# pwrmngmnt.net
KiCad netlist of a schematic drawn in Altium Designer
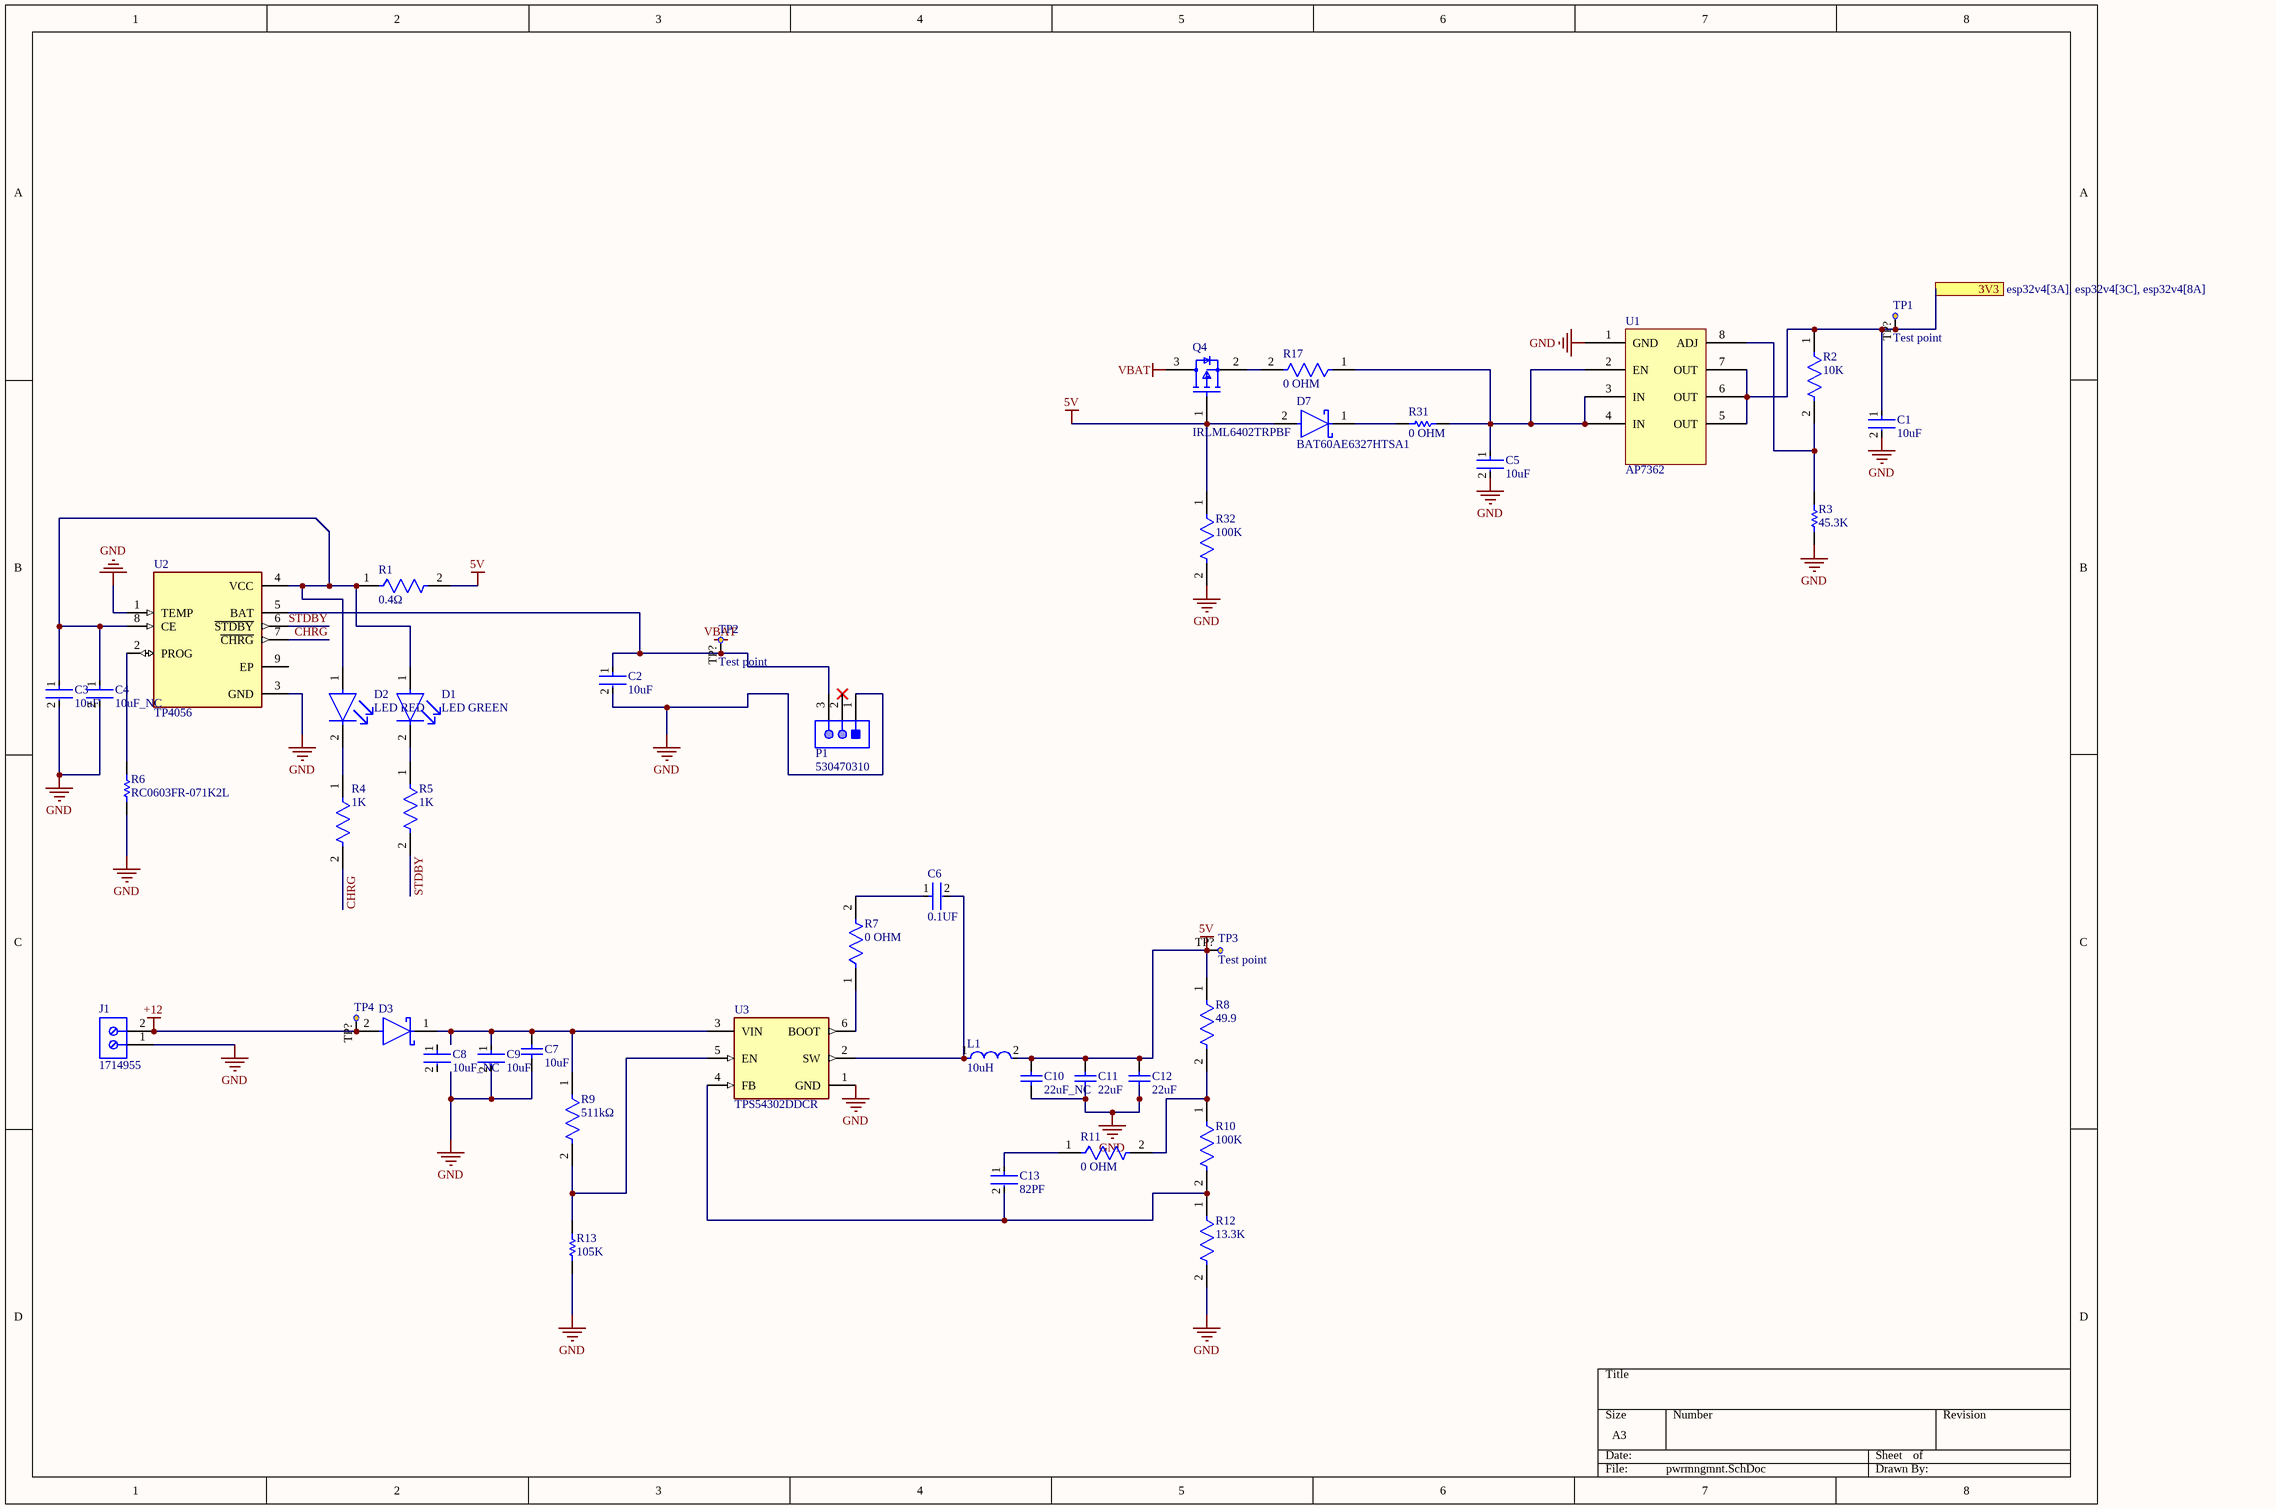
[diagram p0: pwrmngmnt.SchDoc]

(export (version "E")
  (design (tool "Eeschema 10.0.6"))
  (components
    (comp (ref "C1")
      (value "10uF")
      (footprint "FP-GRM21B-0_1-IPC_C")
      (description "Chip Multilayer Ceramic Capacitors for General Purpose, 0805, 10uF, X5R, 15%, 10%, 16V")
      (fields (field (name "TOLERANCE") "10%") (field (name "VOLTAGE") "16V"))
      (libsource (lib "Altium Content Vault") (part "b4654b650e69147ec39a6b967a45e02"))
    )
    (comp (ref "C2")
      (value "10uF")
      (footprint "FP-1210-L_3_3_0_4-W_2_5_0-IPC_B")
      (description "General Purpose Ceramic Capacitor, 1210, 10uF, 10%, X7R, 15%, 50V")
      (fields (field (name "TOLERANCE") "10%") (field (name "VOLTAGE") "50V"))
      (libsource (lib "Altium Content Vault") (part "b4654b650e69147ec39a6b967a45e02"))
    )
    (comp (ref "C3")
      (value "10uF")
      (footprint "FP-GRM21B-0_1-IPC_C")
      (description "Chip Multilayer Ceramic Capacitors for General Purpose, 0805, 10uF, X5R, 15%, 10%, 16V")
      (fields (field (name "TOLERANCE") "10%") (field (name "VOLTAGE") "16V"))
      (libsource (lib "Altium Content Vault") (part "b4654b650e69147ec39a6b967a45e02"))
    )
    (comp (ref "C4")
      (value "10uF_NC")
      (footprint "FP-GRM21B-0_1-IPC_C")
      (description "Chip Multilayer Ceramic Capacitors for General Purpose, 0805, 10uF, X5R, 15%, 10%, 16V")
      (fields (field (name "TOLERANCE") "10%") (field (name "VOLTAGE") "16V"))
      (libsource (lib "Altium Content Vault") (part "b4654b650e69147ec39a6b967a45e02"))
    )
    (comp (ref "C5")
      (value "10uF")
      (footprint "FP-GRM21B-0_1-IPC_C")
      (description "Chip Multilayer Ceramic Capacitors for General Purpose, 0805, 10uF, X5R, 15%, 10%, 16V")
      (fields (field (name "TOLERANCE") "10%") (field (name "VOLTAGE") "16V"))
      (libsource (lib "Altium Content Vault") (part "b4654b650e69147ec39a6b967a45e02"))
    )
    (comp (ref "C6")
      (value "0.1UF")
      (footprint "FP-CC0805-0_85-MFG")
      (description "CAP CER 0.1UF 50V X7R 0805")
      (fields (field (name "TOLERANCE") "0.1") (field (name "MANUFACTURER PART NUMBER") "CC0805KRX7R9BB104"))
      (libsource (lib "Altium Content Vault") (part "11868f565c42a9108669ba33697ecf6"))
    )
    (comp (ref "C7")
      (value "10uF")
      (footprint "CAPC1210(3225)280_L")
      (description "CAP 10uF 25V ±10% 1210 (3225 Metric) Thickness 2.8mm SMD")
      (fields (field (name "TOLERANCE") "Â±10%"))
      (libsource (lib "Altium Content Vault") (part "CAP"))
    )
    (comp (ref "C8")
      (value "10uF_NC")
      (footprint "FP-GRM21B-0_1-IPC_C")
      (description "Chip Multilayer Ceramic Capacitors for General Purpose, 0805, 10uF, X5R, 15%, 10%, 16V")
      (fields (field (name "TOLERANCE") "10%") (field (name "VOLTAGE") "16V"))
      (libsource (lib "Altium Content Vault") (part "b4654b650e69147ec39a6b967a45e02"))
    )
    (comp (ref "C9")
      (value "10uF")
      (footprint "FP-GRM21B-0_1-IPC_C")
      (description "Chip Multilayer Ceramic Capacitors for General Purpose, 0805, 10uF, X5R, 15%, 10%, 16V")
      (fields (field (name "TOLERANCE") "10%") (field (name "VOLTAGE") "16V"))
      (libsource (lib "Altium Content Vault") (part "b4654b650e69147ec39a6b967a45e02"))
    )
    (comp (ref "C10")
      (value "22uF_NC")
      (footprint "CAPC1210(3225)230_L")
      (description "CAP 22uF 16V -20% to +80% 1210 (3225 Metric) Thickness 2.2mm SMD")
      (fields (field (name "TOLERANCE") "-20% to +80%"))
      (libsource (lib "Altium Content Vault") (part "CAP"))
    )
    (comp (ref "C11")
      (value "22uF")
      (footprint "CAPC1210(3225)230_L")
      (description "CAP 22uF 16V -20% to +80% 1210 (3225 Metric) Thickness 2.2mm SMD")
      (fields (field (name "TOLERANCE") "-20% to +80%"))
      (libsource (lib "Altium Content Vault") (part "CAP"))
    )
    (comp (ref "C12")
      (value "22uF")
      (footprint "CAPC1210(3225)230_L")
      (description "CAP 22uF 16V -20% to +80% 1210 (3225 Metric) Thickness 2.2mm SMD")
      (fields (field (name "TOLERANCE") "-20% to +80%"))
      (libsource (lib "Altium Content Vault") (part "CAP"))
    )
    (comp (ref "C13")
      (value "82PF")
      (footprint "FP-C0603C-CF-MFG")
      (description "CAP CER 82PF 50V C0G/NP0 0603")
      (fields (field (name "TOLERANCE") "0.05") (field (name "MANUFACTURER PART NUMBER") "C0603C820J5GACTU"))
      (libsource (lib "Altium Content Vault") (part "b4654b650e69147ec39a6b967a45e02"))
    )
    (comp (ref "D1")
      (value "LED GREEN")
      (footprint "FP-APT2012MGC-MFG")
      (description "LED GREEN CLEAR CHIP SMD")
      (libsource (lib "Altium Content Vault") (part "ab1c01a81903e929fc6c44469aada92"))
    )
    (comp (ref "D2")
      (value "LED RED")
      (footprint "FP-AP2012EC-MFG")
      (description "LED RED CLEAR SMD")
      (libsource (lib "Altium Content Vault") (part "ab1c01a81903e929fc6c44469aada92"))
    )
    (comp (ref "D3")
      (value "SS34-E3/57T")
      (footprint "FP-95402-MFG")
      (description "DIODE SCHOTTKY 40V 3A DO214AB")
      (fields
        (field (name "MANUFACTURER") "Vishay")
        (field (name "OCTOPART") "https://octopart.com/ss34-e3%2F57t-vishay-39552907")
      )
      (libsource (lib "Altium Content Vault") (part "1d6ec82d83fb6aee721767c19dac4b9"))
    )
    (comp (ref "D7")
      (value "BAT60AE6327HTSA1")
      (footprint "FP-PG-SOD323-2-IPC_C")
      (description "DIODE SCHOTTKY 10V 3A SOD323-2")
      (libsource (lib "Altium Content Vault") (part "1d6ec82d83fb6aee721767c19dac4b9"))
    )
    (comp (ref "J1")
      (value "1714955")
      (footprint "PHOE-1714955_V")
      (description "PC Terminal Block, Pitch 6.35 mm, 1 x 2 Position, Height 21.5 mm, Tail Lenght 5.1 mm, RoHS, Bulk")
      (fields (field (name "MANUFACTURER") "Phoenix Contact"))
      (libsource (lib "Altium Content Vault") (part "CN-1P-F-TB2"))
    )
    (comp (ref "L1")
      (value "10uH")
      (footprint "FP-CB3225-IPC_A")
      (description "SMD Inductors 10uH ±20% 0.9A 0.1729Ω 1210")
      (fields (field (name "TOLERANCE") "20%"))
      (libsource (lib "Altium Content Vault") (part "725321dda6339637d4d059423bc1c3c"))
    )
    (comp (ref "P1")
      (value "530470310")
      (footprint "MOLX-530470310_V")
      (fields (field (name "MANUFACTURER") "Molex"))
      (libsource (lib "Altium Content Vault") (part "CN-1P-M-R3"))
    )
    (comp (ref "Q4")
      (value "IRLML6402TRPBF")
      (footprint "FP-Micro3-MFG")
      (description "MOSFET P-CH 20V 3.7A SOT-23")
      (fields
        (field (name "OCTOPART") "https://octopart.com/irlml6402trpbf-infineon-65874989")
        (field (name "MANUFACTURER") "Infineon")
      )
      (libsource (lib "Altium Content Vault") (part "566027c8dc92b5207d53ac25ab3eb60"))
    )
    (comp (ref "R1")
      (value "0.4Ω")
      (footprint "FP-CSR1206-IPC_C")
      (description "General Purpose Thick Film Chip Resistor, 1206, 0.4Ω, 5%, 100ppm/°C, 0.5W")
      (fields (field (name "TOLERANCE") "5%"))
      (libsource (lib "Altium Content Vault") (part "1029c3af85768c4190bb7ad29bc67b5"))
    )
    (comp (ref "R2")
      (value "10K")
      (footprint "FP-RT0603-MFG")
      (description "RES SMD 10K OHM 1% 1/10W 0603")
      (fields
        (field (name "MANUFACTURER") "Yageo")
        (field (name "OCTOPART") "https://octopart.com/rt0603fre0710kl-yageo-40009243")
      )
      (libsource (lib "Altium Content Vault") (part "1029c3af85768c4190bb7ad29bc67b5"))
    )
    (comp (ref "R3")
      (value "45.3K")
      (footprint "RESC2013X60X35NL10T20")
      (fields (field (name "PART NUMBER") "RC0805FR-0745K3L") (field (name "MANUFACTURER") "Yageo"))
      (libsource (lib "Altium Content Vault") (part "RES"))
    )
    (comp (ref "R4")
      (value "1K")
      (footprint "FP-RT0603-MFG")
      (description "RES SMD 1K OHM 0.1% 1/10W 0603")
      (fields
        (field (name "MANUFACTURER PART NUMBER") "RT0603BRD071KL")
        (field (name "MANUFACTURER") "Yageo")
      )
      (libsource (lib "Altium Content Vault") (part "1029c3af85768c4190bb7ad29bc67b5"))
    )
    (comp (ref "R5")
      (value "1K")
      (footprint "FP-RT0603-MFG")
      (description "RES SMD 1K OHM 0.1% 1/10W 0603")
      (fields
        (field (name "MANUFACTURER PART NUMBER") "RT0603BRD071KL")
        (field (name "MANUFACTURER") "Yageo")
      )
      (libsource (lib "Altium Content Vault") (part "1029c3af85768c4190bb7ad29bc67b5"))
    )
    (comp (ref "R6")
      (value "RC0603FR-071K2L")
      (footprint "RESC1608X55X25LL10T15")
      (description "Chip Resistor, 1.2 KOhm, +/- 1%, 0.1 W, -55 to 155 degC, 0603 (1608 Metric), RoHS, Tape and Reel")
      (fields (field (name "TOLERANCE") "1%"))
      (libsource (lib "Altium Content Vault") (part "RES-2"))
    )
    (comp (ref "R7")
      (value "0 OHM")
      (footprint "FP-RMCF0805-MFG")
      (description "RES 0 OHM JUMPER 1/8W 0805")
      (libsource (lib "Altium Content Vault") (part "1029c3af85768c4190bb7ad29bc67b5"))
    )
    (comp (ref "R8")
      (value "49.9")
      (footprint "FP-CPF0603-MFG")
      (description "RES SMD 49.9Ω 1% 1/16W 0603")
      (fields (field (name "TOLERANCE") "1%") (field (name "MANUFACTURER PART NUMBER") "CPF0603F49R9C1"))
      (libsource (lib "Altium Content Vault") (part "1029c3af85768c4190bb7ad29bc67b5"))
    )
    (comp (ref "R9")
      (value "511kΩ")
      (footprint "FP-CRCW0805-e3-IPC_B")
      (description "RES Thick Film, 511kΩ, 1%, 0.125W, 100ppm/°C, 0805")
      (fields (field (name "TOLERANCE") "1%"))
      (libsource (lib "Altium Content Vault") (part "1029c3af85768c4190bb7ad29bc67b5"))
    )
    (comp (ref "R10")
      (value "100K")
      (footprint "FP-RT0402-MFG")
      (description "RES 100K OHM 1/16W .1% SMD 0402")
      (fields (field (name "TOLERANCE") "0.001") (field (name "MANUFACTURER PART NUMBER") "RT0402BRD07100KL"))
      (libsource (lib "Altium Content Vault") (part "1029c3af85768c4190bb7ad29bc67b5"))
    )
    (comp (ref "R11")
      (value "0 OHM")
      (footprint "FP-RMCF0805-MFG")
      (description "RES 0 OHM JUMPER 1/8W 0805")
      (libsource (lib "Altium Content Vault") (part "1029c3af85768c4190bb7ad29bc67b5"))
    )
    (comp (ref "R12")
      (value "13.3K")
      (footprint "FP-ERJ3EK-MFG")
      (fields (field (name "TOLERANCE") "1%"))
      (libsource (lib "Altium Content Vault") (part "1029c3af85768c4190bb7ad29bc67b5"))
    )
    (comp (ref "R13")
      (value "105K")
      (footprint "RESC2013X60X35LL10T20")
      (fields (field (name "PART NUMBER") "RC0805FR-07105KL") (field (name "MANUFACTURER") "Yageo"))
      (libsource (lib "Altium Content Vault") (part "RES"))
    )
    (comp (ref "R17")
      (value "0 OHM")
      (footprint "FP-RMCF0805-MFG")
      (description "RES 0 OHM JUMPER 1/8W 0805")
      (libsource (lib "Altium Content Vault") (part "1029c3af85768c4190bb7ad29bc67b5"))
    )
    (comp (ref "R31")
      (value "0 OHM")
      (footprint "RESC1608X55X25ML10T15")
      (description "Chip Resistor, 0 Ohm, +/- 5%, 0.1 W, -55 to 155 degC, 0603 (1608 Metric), RoHS, Tape and Reel")
      (fields (field (name "TOLERANCE") "5%") (field (name "MANUFACTURER") "Yageo"))
      (libsource (lib "Altium Content Vault") (part "RES-2"))
    )
    (comp (ref "R32")
      (value "100K")
      (footprint "FP-RT0402-MFG")
      (description "RES 100K OHM 1/16W .1% SMD 0402")
      (fields (field (name "TOLERANCE") "0.001") (field (name "MANUFACTURER PART NUMBER") "RT0402BRD07100KL"))
      (libsource (lib "Altium Content Vault") (part "1029c3af85768c4190bb7ad29bc67b5"))
    )
    (comp (ref "TP1")
      (value "Test point")
      (footprint "Test_Point")
      (libsource (lib "Test_Point") (part "Test_Point"))
    )
    (comp (ref "TP2")
      (value "Test point")
      (footprint "Test_Point")
      (libsource (lib "Test_Point") (part "Test_Point"))
    )
    (comp (ref "TP3")
      (value "Test point")
      (footprint "Test_Point")
      (libsource (lib "Test_Point") (part "Test_Point"))
    )
    (comp (ref "TP4")
      (value "Test point")
      (footprint "Test_Point")
      (libsource (lib "Test_Point") (part "Test_Point"))
    )
    (comp (ref "U1")
      (value "AP7362")
      (footprint "SOIC127P600X163-9N")
      (libsource (lib "ap7362") (part "Component_1"))
    )
    (comp (ref "U2")
      (value "TP4056")
      (footprint "SOP127P600X175-9N")
      (description "Complete single cell Li-Ion battery with a constant current / constant voltage linear charger")
      (fields (field (name "MF") "NanJing Top Power ASIC Corp."))
      (libsource (lib "TP4056") (part "TP4056"))
    )
    (comp (ref "U3")
      (value "TPS54302DDCR")
      (footprint "FP-DDC0006A-MFG")
      (description "IC REG BUCK ADJ 3A TSOT23-6")
      (fields
        (field (name "MANUFACTURER") "Texas Instruments")
        (field (name "OCTOPART") "https://octopart.com/tps54302ddcr-texas+instruments-74209025")
      )
      (libsource (lib "Altium Content Vault") (part "e6e62595b56d4ede9a2c24ebe42f01f"))
    )
  )
  (nets
    (net (code "1") (name "+12") (class "Default")
      (node (ref "D3") (pin "2") (pinfunction "A_2") (pintype "passive"))
      (node (ref "J1") (pin "2") (pinfunction "2_2") (pintype "passive"))
      (node (ref "TP4") (pin "TP?") (pinfunction "Test_point_TP?") (pintype "passive"))
    )
    (net (code "2") (name "/3V3") (class "Default")
      (node (ref "C1") (pin "1") (pinfunction "1_1") (pintype "passive"))
      (node (ref "R2") (pin "1") (pinfunction "1_1") (pintype "passive"))
      (node (ref "TP1") (pin "TP?") (pinfunction "Test_point_TP?") (pintype "passive"))
      (node (ref "U1") (pin "5") (pinfunction "OUT_5") (pintype "passive"))
      (node (ref "U1") (pin "6") (pinfunction "OUT_6") (pintype "passive"))
      (node (ref "U1") (pin "7") (pinfunction "OUT_7") (pintype "passive"))
    )
    (net (code "4") (name "/CHRG") (class "Default")
      (node (ref "R4") (pin "2") (pinfunction "2_2") (pintype "passive"))
      (node (ref "U2") (pin "7") (pinfunction "~{CHRG}_7") (pintype "output"))
    )
    (net (code "5") (name "/STDBY") (class "Default")
      (node (ref "R5") (pin "2") (pinfunction "2_2") (pintype "passive"))
      (node (ref "U2") (pin "6") (pinfunction "~{STDBY}_6") (pintype "output"))
    )
    (net (code "6") (name "5V") (class "Default")
      (node (ref "C10") (pin "1") (pinfunction "1_1") (pintype "passive"))
      (node (ref "C11") (pin "1") (pinfunction "1_1") (pintype "passive"))
      (node (ref "C12") (pin "1") (pinfunction "1_1") (pintype "passive"))
      (node (ref "D7") (pin "2") (pinfunction "A_2") (pintype "passive"))
      (node (ref "L1") (pin "2") (pinfunction "2_2") (pintype "passive"))
      (node (ref "Q4") (pin "1") (pinfunction "G_1") (pintype "passive"))
      (node (ref "R1") (pin "2") (pinfunction "2_2") (pintype "passive"))
      (node (ref "R32") (pin "1") (pinfunction "1_1") (pintype "passive"))
      (node (ref "R8") (pin "1") (pinfunction "1_1") (pintype "passive"))
      (node (ref "TP3") (pin "TP?") (pinfunction "Test_point_TP?") (pintype "passive"))
    )
    (net (code "7") (name "GND") (class "Default")
      (node (ref "C1") (pin "2") (pinfunction "2_2") (pintype "passive"))
      (node (ref "C10") (pin "2") (pinfunction "2_2") (pintype "passive"))
      (node (ref "C11") (pin "2") (pinfunction "2_2") (pintype "passive"))
      (node (ref "C12") (pin "2") (pinfunction "2_2") (pintype "passive"))
      (node (ref "C2") (pin "2") (pinfunction "2_2") (pintype "passive"))
      (node (ref "C3") (pin "2") (pinfunction "2_2") (pintype "passive"))
      (node (ref "C4") (pin "2") (pinfunction "2_2") (pintype "passive"))
      (node (ref "C5") (pin "2") (pinfunction "2_2") (pintype "passive"))
      (node (ref "C7") (pin "2") (pinfunction "2_2") (pintype "passive"))
      (node (ref "C9") (pin "2") (pinfunction "2_2") (pintype "passive"))
      (node (ref "J1") (pin "1") (pinfunction "1_1") (pintype "passive"))
      (node (ref "P1") (pin "1") (pinfunction "1_1") (pintype "passive"))
      (node (ref "R12") (pin "2") (pinfunction "2_2") (pintype "passive"))
      (node (ref "R13") (pin "1") (pinfunction "1_1") (pintype "passive"))
      (node (ref "R3") (pin "2") (pinfunction "2_2") (pintype "passive"))
      (node (ref "R32") (pin "2") (pinfunction "2_2") (pintype "passive"))
      (node (ref "R6") (pin "2") (pinfunction "2_2") (pintype "passive"))
      (node (ref "U1") (pin "1") (pinfunction "GND_1") (pintype "passive"))
      (node (ref "U2") (pin "1") (pinfunction "TEMP_1") (pintype "input"))
      (node (ref "U2") (pin "3") (pinfunction "GND_3") (pintype "power_in"))
      (node (ref "U3") (pin "1") (pinfunction "GND_1") (pintype "power_in"))
    )
    (net (code "8") (name "Net-(C6-Pad1)") (class "Default")
      (node (ref "C6") (pin "1") (pinfunction "1_1") (pintype "passive"))
      (node (ref "R7") (pin "2") (pinfunction "2_2") (pintype "passive"))
    )
    (net (code "9") (name "Net-(C13-Pad1)") (class "Default")
      (node (ref "C13") (pin "1") (pinfunction "1_1") (pintype "passive"))
      (node (ref "R11") (pin "1") (pinfunction "1_1") (pintype "passive"))
    )
    (net (code "10") (name "Net-(D1-A)") (class "Default")
      (node (ref "C3") (pin "1") (pinfunction "1_1") (pintype "passive"))
      (node (ref "C4") (pin "1") (pinfunction "1_1") (pintype "passive"))
      (node (ref "D1") (pin "1") (pinfunction "A_1") (pintype "passive"))
      (node (ref "D2") (pin "1") (pinfunction "A_1") (pintype "passive"))
      (node (ref "R1") (pin "1") (pinfunction "1_1") (pintype "passive"))
      (node (ref "U2") (pin "4") (pinfunction "VCC_4") (pintype "power_in"))
      (node (ref "U2") (pin "8") (pinfunction "CE_8") (pintype "input"))
    )
    (net (code "11") (name "Net-(D1-C)") (class "Default")
      (node (ref "D1") (pin "2") (pinfunction "C_2") (pintype "passive"))
      (node (ref "R5") (pin "1") (pinfunction "1_1") (pintype "passive"))
    )
    (net (code "12") (name "Net-(D2-C)") (class "Default")
      (node (ref "D2") (pin "2") (pinfunction "C_2") (pintype "passive"))
      (node (ref "R4") (pin "1") (pinfunction "1_1") (pintype "passive"))
    )
    (net (code "13") (name "Net-(D3-C)") (class "Default")
      (node (ref "C7") (pin "1") (pinfunction "1_1") (pintype "passive"))
      (node (ref "C9") (pin "1") (pinfunction "1_1") (pintype "passive"))
      (node (ref "D3") (pin "1") (pinfunction "C_1") (pintype "passive"))
      (node (ref "R9") (pin "1") (pinfunction "1_1") (pintype "passive"))
      (node (ref "U3") (pin "3") (pinfunction "VIN_3") (pintype "power_in"))
    )
    (net (code "14") (name "Net-(D7-C)") (class "Default")
      (node (ref "D7") (pin "1") (pinfunction "C_1") (pintype "passive"))
      (node (ref "R31") (pin "1") (pinfunction "1_1") (pintype "passive"))
    )
    (net (code "15") (name "Net-(Q4-S)") (class "Default")
      (node (ref "Q4") (pin "2") (pinfunction "S_2") (pintype "passive"))
      (node (ref "R17") (pin "2") (pinfunction "2_2") (pintype "passive"))
    )
    (net (code "16") (name "Net-(R10-Pad1)") (class "Default")
      (node (ref "R10") (pin "1") (pinfunction "1_1") (pintype "passive"))
      (node (ref "R11") (pin "2") (pinfunction "2_2") (pintype "passive"))
      (node (ref "R8") (pin "2") (pinfunction "2_2") (pintype "passive"))
    )
    (net (code "17") (name "Net-(U1-ADJ)") (class "Default")
      (node (ref "R2") (pin "2") (pinfunction "2_2") (pintype "passive"))
      (node (ref "R3") (pin "1") (pinfunction "1_1") (pintype "passive"))
      (node (ref "U1") (pin "8") (pinfunction "ADJ_8") (pintype "passive"))
    )
    (net (code "18") (name "Net-(U1-EN)") (class "Default")
      (node (ref "C5") (pin "1") (pinfunction "1_1") (pintype "passive"))
      (node (ref "R17") (pin "1") (pinfunction "1_1") (pintype "passive"))
      (node (ref "R31") (pin "2") (pinfunction "2_2") (pintype "passive"))
      (node (ref "U1") (pin "2") (pinfunction "EN_2") (pintype "passive"))
      (node (ref "U1") (pin "3") (pinfunction "IN_3") (pintype "passive"))
      (node (ref "U1") (pin "4") (pinfunction "IN_4") (pintype "passive"))
    )
    (net (code "19") (name "Net-(U2-PROG)") (class "Default")
      (node (ref "R6") (pin "1") (pinfunction "1_1") (pintype "passive"))
      (node (ref "U2") (pin "2") (pinfunction "PROG_2") (pintype "bidirectional"))
    )
    (net (code "20") (name "Net-(U3-BOOT)") (class "Default")
      (node (ref "R7") (pin "1") (pinfunction "1_1") (pintype "passive"))
      (node (ref "U3") (pin "6") (pinfunction "BOOT_6") (pintype "output"))
    )
    (net (code "21") (name "Net-(U3-EN)") (class "Default")
      (node (ref "R13") (pin "2") (pinfunction "2_2") (pintype "passive"))
      (node (ref "R9") (pin "2") (pinfunction "2_2") (pintype "passive"))
      (node (ref "U3") (pin "5") (pinfunction "EN_5") (pintype "input"))
    )
    (net (code "22") (name "Net-(U3-FB)") (class "Default")
      (node (ref "C13") (pin "2") (pinfunction "2_2") (pintype "passive"))
      (node (ref "R10") (pin "2") (pinfunction "2_2") (pintype "passive"))
      (node (ref "R12") (pin "1") (pinfunction "1_1") (pintype "passive"))
      (node (ref "U3") (pin "4") (pinfunction "FB_4") (pintype "input"))
    )
    (net (code "23") (name "Net-(U3-SW)") (class "Default")
      (node (ref "C6") (pin "2") (pinfunction "2_2") (pintype "passive"))
      (node (ref "L1") (pin "1") (pinfunction "1_1") (pintype "passive"))
      (node (ref "U3") (pin "2") (pinfunction "SW_2") (pintype "output"))
    )
    (net (code "24") (name "VBAT") (class "Default")
      (node (ref "C2") (pin "1") (pinfunction "1_1") (pintype "passive"))
      (node (ref "P1") (pin "3") (pinfunction "3_3") (pintype "passive"))
      (node (ref "Q4") (pin "3") (pinfunction "D_3") (pintype "passive"))
      (node (ref "TP2") (pin "TP?") (pinfunction "Test_point_TP?") (pintype "passive"))
      (node (ref "U2") (pin "5") (pinfunction "BAT_5") (pintype "power_in"))
    )
    (net (code "25") (name "unconnected-(C8-Pad1)") (class "Default")
      (node (ref "C8") (pin "1") (pinfunction "1_1") (pintype "passive"))
    )
    (net (code "26") (name "unconnected-(C8-Pad2)") (class "Default")
      (node (ref "C8") (pin "2") (pinfunction "2_2") (pintype "passive"))
    )
    (net (code "27") (name "unconnected-(P1-Pad2)") (class "Default")
      (node (ref "P1") (pin "2") (pinfunction "2_2") (pintype "passive+no_connect"))
    )
    (net (code "28") (name "unconnected-(U2-EP-Pad9)") (class "Default")
      (node (ref "U2") (pin "9") (pinfunction "EP_9") (pintype "passive"))
    )
  )
)
